# GPRS.net
KiCad netlist of a schematic drawn in Altium Designer
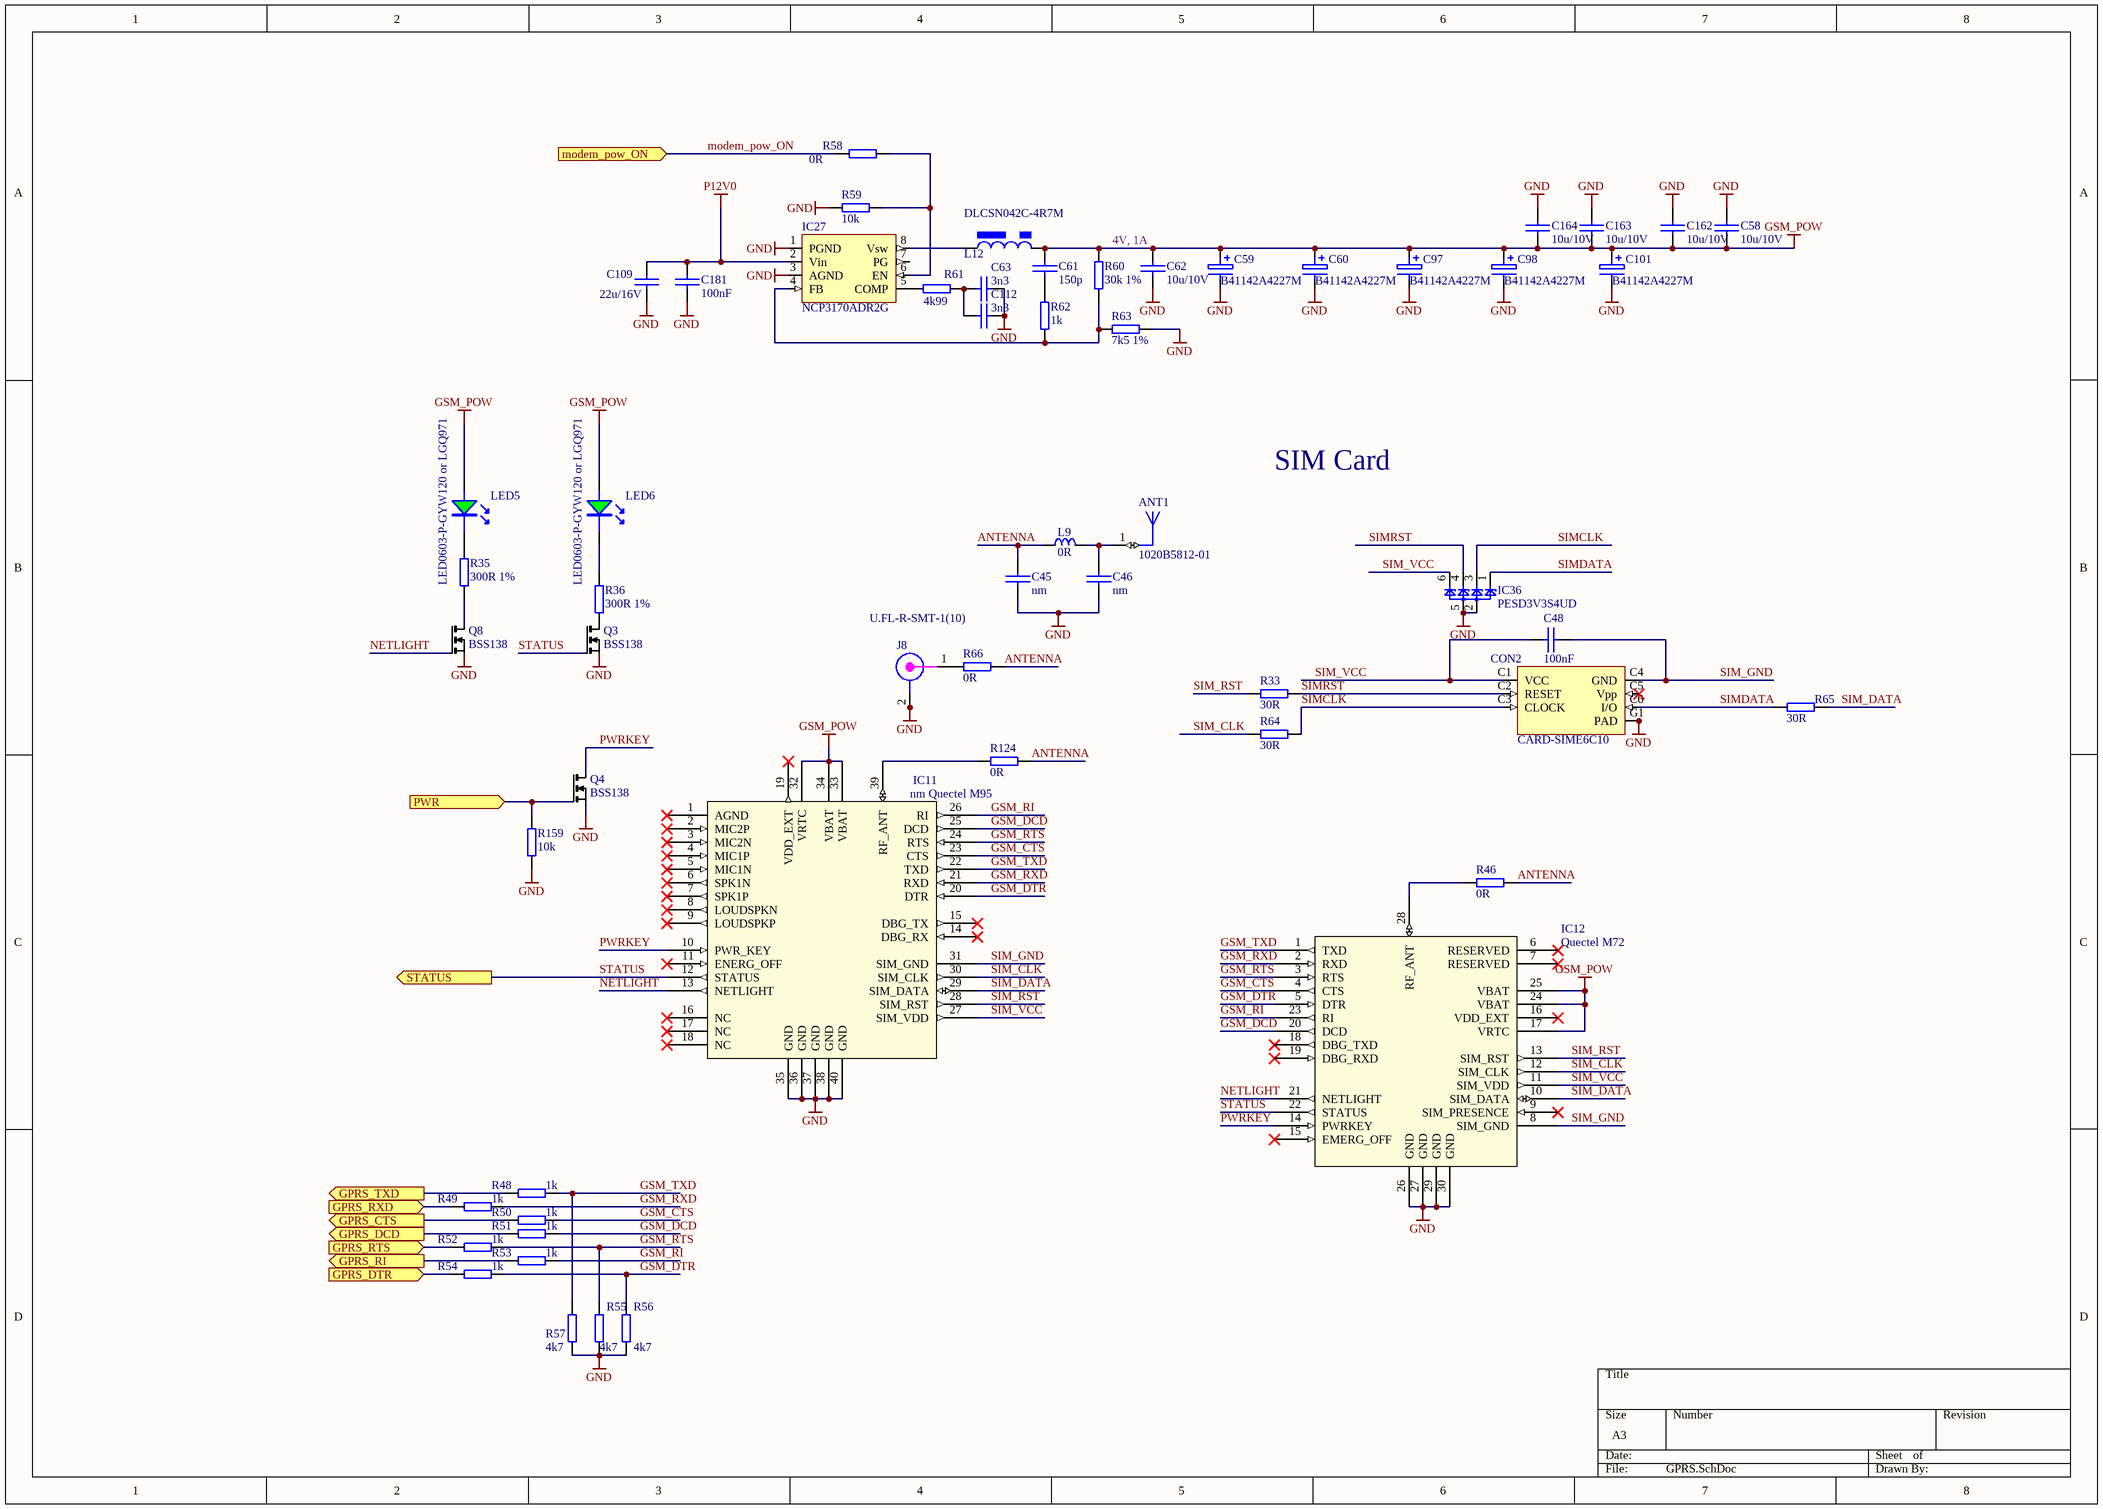
[diagram p0: GPRS.SchDoc]

(export (version "E")
  (design (tool "Eeschema 10.0.6"))
  (components
    (comp (ref "ANT1")
      (value "1020B5812-01")
      (footprint "ANT27.3X7.9")
      (description "Flavus GSM Snap-In Antenna, 800/900/1800/1900 MHz, 0.8mm PCB Thickness")
      (fields (field (name "PUBLISHER") "Altium Limited"))
      (libsource (lib "Antenova RF and IF Antenna") (part "1020B5812-01"))
    )
    (comp (ref "C45")
      (value "nm")
      (footprint "0603C")
      (description "Capacitor SMD")
      (libsource (lib "LIBRARY_SCH") (part "CAP_SMD_0603"))
    )
    (comp (ref "C46")
      (value "nm")
      (footprint "0603C")
      (description "Capacitor SMD")
      (libsource (lib "LIBRARY_SCH") (part "CAP_SMD_0603"))
    )
    (comp (ref "C48")
      (value "100nF")
      (footprint "0402C")
      (description "Capacitor SMD")
      (libsource (lib "LIBRARY_SCH") (part "CAP_SMD_0402"))
    )
    (comp (ref "C58")
      (value "10u/10V")
      (footprint "0805C")
      (description "Capacitor SMD")
      (libsource (lib "*") (part "CAP_SMD"))
    )
    (comp (ref "C59")
      (value "B41142A4227M")
      (footprint "CAP_SMT_EL_5mm_C")
      (description "Electrolytic Capacitor")
      (libsource (lib "LIBRARY_SCH") (part "CAP_ELECTRO_SMD_C"))
    )
    (comp (ref "C60")
      (value "B41142A4227M")
      (footprint "CAP_SMT_EL_5mm_C")
      (description "Electrolytic Capacitor")
      (libsource (lib "LIBRARY_SCH") (part "CAP_ELECTRO_SMD_C"))
    )
    (comp (ref "C61")
      (value "150p")
      (footprint "0603C")
      (description "Capacitor SMD")
      (libsource (lib "LIBRARY_SCH") (part "CAP_SMD_0603"))
    )
    (comp (ref "C62")
      (value "10u/10V")
      (footprint "0805C")
      (description "Capacitor SMD")
      (libsource (lib "LIBRARY_SCH") (part "CAP_SMD"))
    )
    (comp (ref "C63")
      (value "3n3")
      (footprint "0603C")
      (description "Capacitor SMD")
      (libsource (lib "LIBRARY_SCH") (part "CAP_SMD_0603"))
    )
    (comp (ref "C97")
      (value "B41142A4227M")
      (footprint "CAP_SMT_EL_5mm_C")
      (description "Electrolytic Capacitor")
      (libsource (lib "LIBRARY_SCH") (part "CAP_ELECTRO_SMD_C"))
    )
    (comp (ref "C98")
      (value "B41142A4227M")
      (footprint "CAP_SMT_EL_5mm_C")
      (description "Electrolytic Capacitor")
      (libsource (lib "LIBRARY_SCH") (part "CAP_ELECTRO_SMD_C"))
    )
    (comp (ref "C101")
      (value "B41142A4227M")
      (footprint "CAP_SMT_EL_5mm_C")
      (description "Electrolytic Capacitor")
      (libsource (lib "LIBRARY_SCH") (part "CAP_ELECTRO_SMD_C"))
    )
    (comp (ref "C109")
      (value "22u/16V")
      (footprint "1206C")
      (description "Capacitor SMD")
      (libsource (lib "LIBRARY_SCH") (part "CAP_SMD_1206"))
    )
    (comp (ref "C112")
      (value "3n3")
      (footprint "0603C")
      (description "Capacitor SMD")
      (libsource (lib "LIBRARY_SCH") (part "CAP_SMD_0603"))
    )
    (comp (ref "C162")
      (value "10u/10V")
      (footprint "0805C")
      (description "Capacitor SMD")
      (libsource (lib "*") (part "CAP_SMD"))
    )
    (comp (ref "C163")
      (value "10u/10V")
      (footprint "0805C")
      (description "Capacitor SMD")
      (libsource (lib "*") (part "CAP_SMD"))
    )
    (comp (ref "C164")
      (value "10u/10V")
      (footprint "0805C")
      (description "Capacitor SMD")
      (libsource (lib "*") (part "CAP_SMD"))
    )
    (comp (ref "C181")
      (value "100nF")
      (footprint "0402C")
      (description "Capacitor SMD")
      (libsource (lib "LIBRARY_SCH") (part "CAP_SMD_0402"))
    )
    (comp (ref "CON2")
      (value "CARD-SIME6C10")
      (footprint "CON_CARD-SIME6C10")
      (description "Sim Card Holder (Maritex)")
      (libsource (lib "LIBRARY_SCH") (part "CON_CARD-SIME6C10"))
    )
    (comp (ref "IC11")
      (value "nm Quectel M95")
      (footprint "QUECTEL M95")
      (description "GSM Module")
      (libsource (lib "QuectelGSMModule") (part "Quectel M95"))
    )
    (comp (ref "IC12")
      (value "Quectel M72")
      (footprint "Quectel M72 GSM Module")
      (description "GSM Module")
      (libsource (lib "QuectelGSMModule") (part "Quectel M72"))
    )
    (comp (ref "IC27")
      (value "NCP3170ADR2G")
      (footprint "so-8")
      (description "4.5V to 18V, 3A synch buck")
      (libsource (lib "LIBRARY_SCH") (part "PWM_NCP3170"))
    )
    (comp (ref "IC36")
      (value "PESD3V3S4UD")
      (footprint "SOT457")
      (description "3.3V TVS")
      (libsource (lib "LIBRARY_SCH") (part "D_TVS_PESD3V3S4UD"))
    )
    (comp (ref "J8")
      (value "U.FL-R-SMT-1(10)")
      (footprint "CON_UFL_HIROSE_RECEPTACLE")
      (description "UFL")
      (libsource (lib "LIBRARY_SCH") (part "CON_UFL_SMD"))
    )
    (comp (ref "L9")
      (value "0R")
      (footprint "INDC1608X100N")
      (description "Inductor")
      (fields
        (field (name "PART NUMBER") "IND0603_WURTH_74279266")
        (field (name "POWER") "200mA")
        (field (name "AUTHOR") "CERN DEM JLC")
      )
      (libsource (lib "Inductors & Transformers") (part "Inductor"))
    )
    (comp (ref "L12")
      (value "DLCSN042C-4R7M")
      (footprint "L_DLCSN042C")
      (description "inductor (Maritex)")
      (libsource (lib "LIBRARY_SCH") (part "L_POWER_DLCSN042C"))
    )
    (comp (ref "LED5")
      (value "LED0603-P-GYW120 or LGQ971")
      (footprint "led_0603G")
      (description "LED 0603 green")
      (libsource (lib "LIBRARY_SCH") (part "LED_0603G"))
    )
    (comp (ref "LED6")
      (value "LED0603-P-GYW120 or LGQ971")
      (footprint "led_0603G")
      (description "LED 0603 green")
      (libsource (lib "LIBRARY_SCH") (part "LED_0603G"))
    )
    (comp (ref "Q3") (value "BSS138") (footprint "SOT-23") (libsource (lib "LIBRARY_SCH") (part "Q_BSS138")))
    (comp (ref "Q4") (value "BSS138") (footprint "SOT-23") (libsource (lib "LIBRARY_SCH") (part "Q_BSS138")))
    (comp (ref "Q8") (value "BSS138") (footprint "SOT-23") (libsource (lib "LIBRARY_SCH") (part "Q_BSS138")))
    (comp (ref "R33")
      (value "30R")
      (footprint "0603R")
      (description "SMD Resistor")
      (libsource (lib "*") (part "RES_SMD"))
    )
    (comp (ref "R35")
      (value "300R 1%")
      (footprint "0603R")
      (description "SMD Resistor")
      (libsource (lib "") (part "RES_0603_1"))
    )
    (comp (ref "R36")
      (value "300R 1%")
      (footprint "0603R")
      (description "SMD Resistor")
      (libsource (lib "") (part "RES_0603_1"))
    )
    (comp (ref "R46")
      (value "0R")
      (footprint "0603R")
      (description "SMD Resistor")
      (libsource (lib "*") (part "RES_SMD"))
    )
    (comp (ref "R48")
      (value "1k")
      (footprint "0402R")
      (description "SMD Resistor")
      (libsource (lib "LIBRARY_SCH") (part "RES_0402"))
    )
    (comp (ref "R49")
      (value "1k")
      (footprint "0402R")
      (description "SMD Resistor")
      (libsource (lib "LIBRARY_SCH") (part "RES_0402"))
    )
    (comp (ref "R50")
      (value "1k")
      (footprint "0402R")
      (description "SMD Resistor")
      (libsource (lib "LIBRARY_SCH") (part "RES_0402"))
    )
    (comp (ref "R51")
      (value "1k")
      (footprint "0402R")
      (description "SMD Resistor")
      (libsource (lib "LIBRARY_SCH") (part "RES_0402"))
    )
    (comp (ref "R52")
      (value "1k")
      (footprint "0402R")
      (description "SMD Resistor")
      (libsource (lib "LIBRARY_SCH") (part "RES_0402"))
    )
    (comp (ref "R53")
      (value "1k")
      (footprint "0402R")
      (description "SMD Resistor")
      (libsource (lib "LIBRARY_SCH") (part "RES_0402"))
    )
    (comp (ref "R54")
      (value "1k")
      (footprint "0402R")
      (description "SMD Resistor")
      (libsource (lib "LIBRARY_SCH") (part "RES_0402"))
    )
    (comp (ref "R55")
      (value "4k7")
      (footprint "0402R")
      (description "SMD Resistor")
      (libsource (lib "LIBRARY_SCH") (part "RES_0402"))
    )
    (comp (ref "R56")
      (value "4k7")
      (footprint "0402R")
      (description "SMD Resistor")
      (libsource (lib "LIBRARY_SCH") (part "RES_0402"))
    )
    (comp (ref "R57")
      (value "4k7")
      (footprint "0402R")
      (description "SMD Resistor")
      (libsource (lib "LIBRARY_SCH") (part "RES_0402"))
    )
    (comp (ref "R58")
      (value "0R")
      (footprint "0603R")
      (description "SMD Resistor")
      (libsource (lib "LIBRARY_SCH") (part "RES_SMD"))
    )
    (comp (ref "R59")
      (value "10k")
      (footprint "0402R")
      (description "SMD Resistor")
      (libsource (lib "LIBRARY_SCH") (part "RES_SMD"))
    )
    (comp (ref "R60")
      (value "30k 1%")
      (footprint "0603R")
      (description "SMD Resistor")
      (libsource (lib "LIBRARY_SCH") (part "RES_0603"))
    )
    (comp (ref "R61")
      (value "4k99")
      (footprint "0603R")
      (description "SMD Resistor")
      (libsource (lib "LIBRARY_SCH") (part "RES_0603"))
    )
    (comp (ref "R62")
      (value "1k")
      (footprint "0402R")
      (description "SMD Resistor")
      (libsource (lib "LIBRARY_SCH") (part "RES_0402"))
    )
    (comp (ref "R63")
      (value "7k5 1%")
      (footprint "0603R")
      (description "SMD Resistor")
      (libsource (lib "LIBRARY_SCH") (part "RES_0603"))
    )
    (comp (ref "R64")
      (value "30R")
      (footprint "0603R")
      (description "SMD Resistor")
      (libsource (lib "*") (part "RES_SMD"))
    )
    (comp (ref "R65")
      (value "30R")
      (footprint "0603R")
      (description "SMD Resistor")
      (libsource (lib "*") (part "RES_SMD"))
    )
    (comp (ref "R66")
      (value "0R")
      (footprint "0603R")
      (description "SMD Resistor")
      (libsource (lib "*") (part "RES_SMD"))
    )
    (comp (ref "R124")
      (value "0R")
      (footprint "0603R")
      (description "SMD Resistor")
      (libsource (lib "*") (part "RES_SMD"))
    )
    (comp (ref "R159")
      (value "10k")
      (footprint "0402R")
      (description "SMD Resistor")
      (libsource (lib "LIBRARY_SCH") (part "RES_0402"))
    )
  )
  (nets
    (net (code "1") (name "/ANTENNA") (class "Default")
      (node (ref "C45") (pin "1") (pinfunction "1_1") (pintype "passive"))
      (node (ref "L9") (pin "1") (pinfunction "1_1") (pintype "passive"))
      (node (ref "R124") (pin "1") (pinfunction "1_1") (pintype "passive"))
      (node (ref "R46") (pin "1") (pinfunction "1_1") (pintype "passive"))
      (node (ref "R66") (pin "1") (pinfunction "1_1") (pintype "passive"))
    )
    (net (code "2") (name "/GPRS_CTS") (class "Default")
      (node (ref "R50") (pin "1") (pinfunction "1_1") (pintype "passive"))
    )
    (net (code "3") (name "/GPRS_DCD") (class "Default")
      (node (ref "R51") (pin "1") (pinfunction "1_1") (pintype "passive"))
    )
    (net (code "4") (name "/GPRS_DTR") (class "Default")
      (node (ref "R54") (pin "1") (pinfunction "1_1") (pintype "passive"))
    )
    (net (code "5") (name "/GPRS_RI") (class "Default")
      (node (ref "R53") (pin "1") (pinfunction "1_1") (pintype "passive"))
    )
    (net (code "6") (name "/GPRS_RTS") (class "Default")
      (node (ref "R52") (pin "1") (pinfunction "1_1") (pintype "passive"))
    )
    (net (code "7") (name "/GPRS_RXD") (class "Default")
      (node (ref "R49") (pin "1") (pinfunction "1_1") (pintype "passive"))
    )
    (net (code "8") (name "/GPRS_TXD") (class "Default")
      (node (ref "R48") (pin "1") (pinfunction "1_1") (pintype "passive"))
    )
    (net (code "9") (name "/GSM_CTS") (class "Default")
      (node (ref "IC11") (pin "23") (pinfunction "CTS_23") (pintype "output"))
      (node (ref "IC12") (pin "4") (pinfunction "CTS_4") (pintype "output"))
      (node (ref "R50") (pin "2") (pinfunction "2_2") (pintype "passive"))
    )
    (net (code "10") (name "/GSM_DCD") (class "Default")
      (node (ref "IC11") (pin "25") (pinfunction "DCD_25") (pintype "output"))
      (node (ref "IC12") (pin "20") (pinfunction "DCD_20") (pintype "output"))
      (node (ref "R51") (pin "2") (pinfunction "2_2") (pintype "passive"))
    )
    (net (code "11") (name "/GSM_DTR") (class "Default")
      (node (ref "IC11") (pin "20") (pinfunction "DTR_20") (pintype "input"))
      (node (ref "IC12") (pin "5") (pinfunction "DTR_5") (pintype "input"))
      (node (ref "R54") (pin "2") (pinfunction "2_2") (pintype "passive"))
      (node (ref "R56") (pin "2") (pinfunction "2_2") (pintype "passive"))
    )
    (net (code "12") (name "/GSM_RI") (class "Default")
      (node (ref "IC11") (pin "26") (pinfunction "RI_26") (pintype "output"))
      (node (ref "IC12") (pin "23") (pinfunction "RI_23") (pintype "output"))
      (node (ref "R53") (pin "2") (pinfunction "2_2") (pintype "passive"))
    )
    (net (code "13") (name "/GSM_RTS") (class "Default")
      (node (ref "IC11") (pin "24") (pinfunction "RTS_24") (pintype "input"))
      (node (ref "IC12") (pin "3") (pinfunction "RTS_3") (pintype "input"))
      (node (ref "R52") (pin "2") (pinfunction "2_2") (pintype "passive"))
      (node (ref "R55") (pin "2") (pinfunction "2_2") (pintype "passive"))
    )
    (net (code "14") (name "/GSM_RXD") (class "Default")
      (node (ref "IC11") (pin "21") (pinfunction "RXD_21") (pintype "input"))
      (node (ref "IC12") (pin "2") (pinfunction "RXD_2") (pintype "input"))
      (node (ref "R49") (pin "2") (pinfunction "2_2") (pintype "passive"))
    )
    (net (code "15") (name "/GSM_TXD") (class "Default")
      (node (ref "IC11") (pin "22") (pinfunction "TXD_22") (pintype "output"))
      (node (ref "IC12") (pin "1") (pinfunction "TXD_1") (pintype "output"))
      (node (ref "R48") (pin "2") (pinfunction "2_2") (pintype "passive"))
      (node (ref "R57") (pin "2") (pinfunction "2_2") (pintype "passive"))
    )
    (net (code "16") (name "/NETLIGHT") (class "Default")
      (node (ref "IC11") (pin "13") (pinfunction "NETLIGHT_13") (pintype "output"))
      (node (ref "IC12") (pin "21") (pinfunction "NETLIGHT_21") (pintype "output"))
      (node (ref "Q8") (pin "1") (pinfunction "G_1") (pintype "input"))
    )
    (net (code "17") (name "/PWR") (class "Default")
      (node (ref "Q4") (pin "1") (pinfunction "G_1") (pintype "input"))
      (node (ref "R159") (pin "1") (pinfunction "1_1") (pintype "passive"))
    )
    (net (code "18") (name "/PWRKEY") (class "Default")
      (node (ref "IC11") (pin "10") (pinfunction "PWR_KEY_10") (pintype "input"))
      (node (ref "IC12") (pin "14") (pinfunction "PWRKEY_14") (pintype "input"))
      (node (ref "Q4") (pin "3") (pinfunction "D_3") (pintype "passive"))
    )
    (net (code "19") (name "/SIMCLK") (class "Default")
      (node (ref "CON2") (pin "C3") (pinfunction "CLOCK_C3") (pintype "input"))
      (node (ref "IC36") (pin "3") (pinfunction "3_3") (pintype "passive"))
      (node (ref "R64") (pin "2") (pinfunction "2_2") (pintype "passive"))
    )
    (net (code "20") (name "/SIMDATA") (class "Default")
      (node (ref "CON2") (pin "C6") (pinfunction "I/O_C6") (pintype "input"))
      (node (ref "IC36") (pin "1") (pinfunction "1_1") (pintype "passive"))
      (node (ref "R65") (pin "2") (pinfunction "2_2") (pintype "passive"))
    )
    (net (code "21") (name "/SIMRST") (class "Default")
      (node (ref "CON2") (pin "C2") (pinfunction "RESET_C2") (pintype "input"))
      (node (ref "IC36") (pin "4") (pinfunction "4_4") (pintype "passive"))
      (node (ref "R33") (pin "1") (pinfunction "1_1") (pintype "passive"))
    )
    (net (code "22") (name "/SIM_CLK") (class "Default")
      (node (ref "IC11") (pin "30") (pinfunction "SIM_CLK_30") (pintype "output"))
      (node (ref "IC12") (pin "12") (pinfunction "SIM_CLK_12") (pintype "output"))
      (node (ref "R64") (pin "1") (pinfunction "1_1") (pintype "passive"))
    )
    (net (code "23") (name "/SIM_DATA") (class "Default")
      (node (ref "IC11") (pin "29") (pinfunction "SIM_DATA_29") (pintype "bidirectional"))
      (node (ref "IC12") (pin "10") (pinfunction "SIM_DATA_10") (pintype "bidirectional"))
      (node (ref "R65") (pin "1") (pinfunction "1_1") (pintype "passive"))
    )
    (net (code "24") (name "/SIM_GND") (class "Default")
      (node (ref "C48") (pin "2") (pinfunction "2_2") (pintype "passive"))
      (node (ref "CON2") (pin "C4") (pinfunction "GND_C4") (pintype "power_in"))
      (node (ref "IC11") (pin "31") (pinfunction "SIM_GND_31") (pintype "passive"))
      (node (ref "IC12") (pin "8") (pinfunction "SIM_GND_8") (pintype "power_in"))
    )
    (net (code "25") (name "/SIM_RST") (class "Default")
      (node (ref "IC11") (pin "28") (pinfunction "SIM_RST_28") (pintype "output"))
      (node (ref "IC12") (pin "13") (pinfunction "SIM_RST_13") (pintype "output"))
      (node (ref "R33") (pin "2") (pinfunction "2_2") (pintype "passive"))
    )
    (net (code "26") (name "/SIM_VCC") (class "Default")
      (node (ref "C48") (pin "1") (pinfunction "1_1") (pintype "passive"))
      (node (ref "CON2") (pin "C1") (pinfunction "VCC_C1") (pintype "power_in"))
      (node (ref "IC11") (pin "27") (pinfunction "SIM_VDD_27") (pintype "output"))
      (node (ref "IC12") (pin "11") (pinfunction "SIM_VDD_11") (pintype "output"))
      (node (ref "IC36") (pin "6") (pinfunction "6_6") (pintype "passive"))
    )
    (net (code "27") (name "/STATUS") (class "Default")
      (node (ref "IC11") (pin "12") (pinfunction "STATUS_12") (pintype "output"))
      (node (ref "IC12") (pin "22") (pinfunction "STATUS_22") (pintype "output"))
      (node (ref "Q3") (pin "1") (pinfunction "G_1") (pintype "input"))
    )
    (net (code "28") (name "/modem_pow_ON") (class "Default")
      (node (ref "R58") (pin "1") (pinfunction "1_1") (pintype "passive"))
    )
    (net (code "29") (name "GND") (class "Default")
      (node (ref "C101") (pin "2") (pinfunction "2_2") (pintype "passive"))
      (node (ref "C109") (pin "2") (pinfunction "2_2") (pintype "passive"))
      (node (ref "C112") (pin "2") (pinfunction "2_2") (pintype "passive"))
      (node (ref "C162") (pin "1") (pinfunction "1_1") (pintype "passive"))
      (node (ref "C163") (pin "1") (pinfunction "1_1") (pintype "passive"))
      (node (ref "C164") (pin "1") (pinfunction "1_1") (pintype "passive"))
      (node (ref "C181") (pin "1") (pinfunction "1_1") (pintype "passive"))
      (node (ref "C45") (pin "2") (pinfunction "2_2") (pintype "passive"))
      (node (ref "C46") (pin "2") (pinfunction "2_2") (pintype "passive"))
      (node (ref "C58") (pin "1") (pinfunction "1_1") (pintype "passive"))
      (node (ref "C59") (pin "2") (pinfunction "2_2") (pintype "passive"))
      (node (ref "C60") (pin "2") (pinfunction "2_2") (pintype "passive"))
      (node (ref "C62") (pin "2") (pinfunction "2_2") (pintype "passive"))
      (node (ref "C63") (pin "2") (pinfunction "2_2") (pintype "passive"))
      (node (ref "C97") (pin "2") (pinfunction "2_2") (pintype "passive"))
      (node (ref "C98") (pin "2") (pinfunction "2_2") (pintype "passive"))
      (node (ref "CON2") (pin "G1") (pinfunction "PAD_G1") (pintype "passive"))
      (node (ref "CON2") (pin "G2") (pinfunction "GND_G2") (pintype "passive"))
      (node (ref "CON2") (pin "G3") (pinfunction "GND_G3") (pintype "passive"))
      (node (ref "CON2") (pin "G4") (pinfunction "GND_G4") (pintype "passive"))
      (node (ref "IC11") (pin "35") (pinfunction "GND_35") (pintype "passive"))
      (node (ref "IC11") (pin "36") (pinfunction "GND_36") (pintype "passive"))
      (node (ref "IC11") (pin "37") (pinfunction "GND_37") (pintype "passive"))
      (node (ref "IC11") (pin "38") (pinfunction "GND_38") (pintype "passive"))
      (node (ref "IC11") (pin "40") (pinfunction "GND_40") (pintype "passive"))
      (node (ref "IC12") (pin "26") (pinfunction "GND_26") (pintype "power_in"))
      (node (ref "IC12") (pin "27") (pinfunction "GND_27") (pintype "power_in"))
      (node (ref "IC12") (pin "29") (pinfunction "GND_29") (pintype "power_in"))
      (node (ref "IC12") (pin "30") (pinfunction "GND_30") (pintype "power_in"))
      (node (ref "IC27") (pin "1") (pinfunction "PGND_1") (pintype "power_in"))
      (node (ref "IC27") (pin "3") (pinfunction "AGND_3") (pintype "power_in"))
      (node (ref "IC36") (pin "2") (pinfunction "2_2") (pintype "passive"))
      (node (ref "IC36") (pin "5") (pinfunction "5_5") (pintype "passive"))
      (node (ref "J8") (pin "2") (pintype "passive"))
      (node (ref "J8") (pin "2a") (pinfunction "GND_2a") (pintype "passive"))
      (node (ref "Q3") (pin "2") (pinfunction "S_2") (pintype "passive"))
      (node (ref "Q4") (pin "2") (pinfunction "S_2") (pintype "passive"))
      (node (ref "Q8") (pin "2") (pinfunction "S_2") (pintype "passive"))
      (node (ref "R159") (pin "2") (pinfunction "2_2") (pintype "passive"))
      (node (ref "R55") (pin "1") (pinfunction "1_1") (pintype "passive"))
      (node (ref "R56") (pin "1") (pinfunction "1_1") (pintype "passive"))
      (node (ref "R57") (pin "1") (pinfunction "1_1") (pintype "passive"))
      (node (ref "R59") (pin "1") (pinfunction "1_1") (pintype "passive"))
      (node (ref "R63") (pin "1") (pinfunction "1_1") (pintype "passive"))
    )
    (net (code "30") (name "GSM_POW") (class "Default")
      (node (ref "C101") (pin "1") (pinfunction "1_1") (pintype "passive"))
      (node (ref "C162") (pin "2") (pinfunction "2_2") (pintype "passive"))
      (node (ref "C163") (pin "2") (pinfunction "2_2") (pintype "passive"))
      (node (ref "C164") (pin "2") (pinfunction "2_2") (pintype "passive"))
      (node (ref "C58") (pin "2") (pinfunction "2_2") (pintype "passive"))
      (node (ref "C59") (pin "1") (pinfunction "1_1") (pintype "passive"))
      (node (ref "C60") (pin "1") (pinfunction "1_1") (pintype "passive"))
      (node (ref "C61") (pin "1") (pinfunction "1_1") (pintype "passive"))
      (node (ref "C62") (pin "1") (pinfunction "1_1") (pintype "passive"))
      (node (ref "C97") (pin "1") (pinfunction "1_1") (pintype "passive"))
      (node (ref "C98") (pin "1") (pinfunction "1_1") (pintype "passive"))
      (node (ref "IC11") (pin "32") (pinfunction "VRTC_32") (pintype "power_in"))
      (node (ref "IC11") (pin "33") (pinfunction "VBAT_33") (pintype "power_in"))
      (node (ref "IC11") (pin "34") (pinfunction "VBAT_34") (pintype "power_in"))
      (node (ref "IC12") (pin "17") (pinfunction "VRTC_17") (pintype "power_in"))
      (node (ref "IC12") (pin "24") (pinfunction "VBAT_24") (pintype "power_in"))
      (node (ref "IC12") (pin "25") (pinfunction "VBAT_25") (pintype "power_in"))
      (node (ref "L12") (pin "2") (pintype "passive"))
      (node (ref "LED5") (pin "A") (pinfunction "A_A") (pintype "passive"))
      (node (ref "LED6") (pin "A") (pinfunction "A_A") (pintype "passive"))
      (node (ref "R60") (pin "2") (pinfunction "2_2") (pintype "passive"))
    )
    (net (code "31") (name "Net-(ANT1-FEED)") (class "Default")
      (node (ref "ANT1") (pin "1") (pinfunction "FEED_1") (pintype "bidirectional"))
      (node (ref "C46") (pin "1") (pinfunction "1_1") (pintype "passive"))
      (node (ref "L9") (pin "2") (pinfunction "2_2") (pintype "passive"))
    )
    (net (code "32") (name "Net-(C61-Pad2)") (class "Default")
      (node (ref "C61") (pin "2") (pinfunction "2_2") (pintype "passive"))
      (node (ref "R62") (pin "1") (pinfunction "1_1") (pintype "passive"))
    )
    (net (code "33") (name "Net-(C112-Pad1)") (class "Default")
      (node (ref "C112") (pin "1") (pinfunction "1_1") (pintype "passive"))
      (node (ref "C63") (pin "1") (pinfunction "1_1") (pintype "passive"))
      (node (ref "R61") (pin "1") (pinfunction "1_1") (pintype "passive"))
    )
    (net (code "34") (name "Net-(IC11-RF_ANT)") (class "Default")
      (node (ref "IC11") (pin "39") (pinfunction "RF_ANT_39") (pintype "bidirectional"))
      (node (ref "R124") (pin "2") (pinfunction "2_2") (pintype "passive"))
    )
    (net (code "35") (name "Net-(IC12-RF_ANT)") (class "Default")
      (node (ref "IC12") (pin "28") (pinfunction "RF_ANT_28") (pintype "bidirectional"))
      (node (ref "R46") (pin "2") (pinfunction "2_2") (pintype "passive"))
    )
    (net (code "36") (name "Net-(IC27-COMP)") (class "Default")
      (node (ref "IC27") (pin "5") (pinfunction "COMP_5") (pintype "passive"))
      (node (ref "R61") (pin "2") (pinfunction "2_2") (pintype "passive"))
    )
    (net (code "37") (name "Net-(IC27-EN)") (class "Default")
      (node (ref "IC27") (pin "6") (pinfunction "EN_6") (pintype "input"))
      (node (ref "R58") (pin "2") (pinfunction "2_2") (pintype "passive"))
      (node (ref "R59") (pin "2") (pinfunction "2_2") (pintype "passive"))
    )
    (net (code "38") (name "Net-(IC27-FB)") (class "Default")
      (node (ref "IC27") (pin "4") (pinfunction "FB_4") (pintype "input"))
      (node (ref "R60") (pin "1") (pinfunction "1_1") (pintype "passive"))
      (node (ref "R62") (pin "2") (pinfunction "2_2") (pintype "passive"))
      (node (ref "R63") (pin "2") (pinfunction "2_2") (pintype "passive"))
    )
    (net (code "39") (name "Net-(IC27-Vsw)") (class "Default")
      (node (ref "IC27") (pin "8") (pinfunction "Vsw_8") (pintype "output"))
      (node (ref "L12") (pin "1") (pintype "passive"))
    )
    (net (code "40") (name "Net-(J8-Pad1)") (class "Default")
      (node (ref "J8") (pin "1") (pintype "passive"))
      (node (ref "R66") (pin "2") (pinfunction "2_2") (pintype "passive"))
    )
    (net (code "41") (name "Net-(LED5-PadK)") (class "Default")
      (node (ref "LED5") (pin "K") (pinfunction "K_K") (pintype "passive"))
      (node (ref "R35") (pin "2") (pinfunction "2_2") (pintype "passive"))
    )
    (net (code "42") (name "Net-(LED6-PadK)") (class "Default")
      (node (ref "LED6") (pin "K") (pinfunction "K_K") (pintype "passive"))
      (node (ref "R36") (pin "2") (pinfunction "2_2") (pintype "passive"))
    )
    (net (code "43") (name "Net-(Q3-D)") (class "Default")
      (node (ref "Q3") (pin "3") (pinfunction "D_3") (pintype "passive"))
      (node (ref "R36") (pin "1") (pinfunction "1_1") (pintype "passive"))
    )
    (net (code "44") (name "Net-(Q8-D)") (class "Default")
      (node (ref "Q8") (pin "3") (pinfunction "D_3") (pintype "passive"))
      (node (ref "R35") (pin "1") (pinfunction "1_1") (pintype "passive"))
    )
    (net (code "45") (name "P12V0") (class "Default")
      (node (ref "C109") (pin "1") (pinfunction "1_1") (pintype "passive"))
      (node (ref "C181") (pin "2") (pinfunction "2_2") (pintype "passive"))
      (node (ref "IC27") (pin "2") (pinfunction "Vin_2") (pintype "power_in"))
    )
    (net (code "46") (name "unconnected-(CON2-Vpp-PadC5)") (class "Default")
      (node (ref "CON2") (pin "C5") (pinfunction "Vpp_C5") (pintype "input+no_connect"))
    )
    (net (code "47") (name "unconnected-(IC11-AGND-Pad1)") (class "Default")
      (node (ref "IC11") (pin "1") (pinfunction "AGND_1") (pintype "passive+no_connect"))
    )
    (net (code "48") (name "unconnected-(IC11-DBG_RX-Pad14)") (class "Default")
      (node (ref "IC11") (pin "14") (pinfunction "DBG_RX_14") (pintype "input+no_connect"))
    )
    (net (code "49") (name "unconnected-(IC11-DBG_TX-Pad15)") (class "Default")
      (node (ref "IC11") (pin "15") (pinfunction "DBG_TX_15") (pintype "output+no_connect"))
    )
    (net (code "50") (name "unconnected-(IC11-ENERG_OFF-Pad11)") (class "Default")
      (node (ref "IC11") (pin "11") (pinfunction "ENERG_OFF_11") (pintype "input+no_connect"))
    )
    (net (code "51") (name "unconnected-(IC11-LOUDSPKN-Pad8)") (class "Default")
      (node (ref "IC11") (pin "8") (pinfunction "LOUDSPKN_8") (pintype "output+no_connect"))
    )
    (net (code "52") (name "unconnected-(IC11-LOUDSPKP-Pad9)") (class "Default")
      (node (ref "IC11") (pin "9") (pinfunction "LOUDSPKP_9") (pintype "output+no_connect"))
    )
    (net (code "53") (name "unconnected-(IC11-MIC1N-Pad5)") (class "Default")
      (node (ref "IC11") (pin "5") (pinfunction "MIC1N_5") (pintype "input+no_connect"))
    )
    (net (code "54") (name "unconnected-(IC11-MIC1P-Pad4)") (class "Default")
      (node (ref "IC11") (pin "4") (pinfunction "MIC1P_4") (pintype "input+no_connect"))
    )
    (net (code "55") (name "unconnected-(IC11-MIC2N-Pad3)") (class "Default")
      (node (ref "IC11") (pin "3") (pinfunction "MIC2N_3") (pintype "input+no_connect"))
    )
    (net (code "56") (name "unconnected-(IC11-MIC2P-Pad2)") (class "Default")
      (node (ref "IC11") (pin "2") (pinfunction "MIC2P_2") (pintype "input+no_connect"))
    )
    (net (code "57") (name "unconnected-(IC11-NC-Pad16)") (class "Default")
      (node (ref "IC11") (pin "16") (pinfunction "NC_16") (pintype "passive+no_connect"))
    )
    (net (code "58") (name "unconnected-(IC11-NC-Pad17)") (class "Default")
      (node (ref "IC11") (pin "17") (pinfunction "NC_17") (pintype "passive+no_connect"))
    )
    (net (code "59") (name "unconnected-(IC11-NC-Pad18)") (class "Default")
      (node (ref "IC11") (pin "18") (pinfunction "NC_18") (pintype "passive+no_connect"))
    )
    (net (code "60") (name "unconnected-(IC11-SPK1N-Pad6)") (class "Default")
      (node (ref "IC11") (pin "6") (pinfunction "SPK1N_6") (pintype "output+no_connect"))
    )
    (net (code "61") (name "unconnected-(IC11-SPK1P-Pad7)") (class "Default")
      (node (ref "IC11") (pin "7") (pinfunction "SPK1P_7") (pintype "output+no_connect"))
    )
    (net (code "62") (name "unconnected-(IC11-VDD_EXT-Pad19)") (class "Default")
      (node (ref "IC11") (pin "19") (pinfunction "VDD_EXT_19") (pintype "output+no_connect"))
    )
    (net (code "63") (name "unconnected-(IC12-DBG_RXD-Pad19)") (class "Default")
      (node (ref "IC12") (pin "19") (pinfunction "DBG_RXD_19") (pintype "input+no_connect"))
    )
    (net (code "64") (name "unconnected-(IC12-DBG_TXD-Pad18)") (class "Default")
      (node (ref "IC12") (pin "18") (pinfunction "DBG_TXD_18") (pintype "output+no_connect"))
    )
    (net (code "65") (name "unconnected-(IC12-EMERG_OFF-Pad15)") (class "Default")
      (node (ref "IC12") (pin "15") (pinfunction "EMERG_OFF_15") (pintype "input+no_connect"))
    )
    (net (code "66") (name "unconnected-(IC12-RESERVED-Pad6)") (class "Default")
      (node (ref "IC12") (pin "6") (pinfunction "RESERVED_6") (pintype "passive+no_connect"))
    )
    (net (code "67") (name "unconnected-(IC12-RESERVED-Pad7)") (class "Default")
      (node (ref "IC12") (pin "7") (pinfunction "RESERVED_7") (pintype "passive+no_connect"))
    )
    (net (code "68") (name "unconnected-(IC12-SIM_PRESENCE-Pad9)") (class "Default")
      (node (ref "IC12") (pin "9") (pinfunction "SIM_PRESENCE_9") (pintype "input+no_connect"))
    )
    (net (code "69") (name "unconnected-(IC12-VDD_EXT-Pad16)") (class "Default")
      (node (ref "IC12") (pin "16") (pinfunction "VDD_EXT_16") (pintype "power_in+no_connect"))
    )
    (net (code "70") (name "unconnected-(IC27-PG-Pad7)") (class "Default")
      (node (ref "IC27") (pin "7") (pinfunction "PG_7") (pintype "output"))
    )
  )
)
